# brain_rev_101.net
KiCad netlist of a schematic drawn in EAGLE
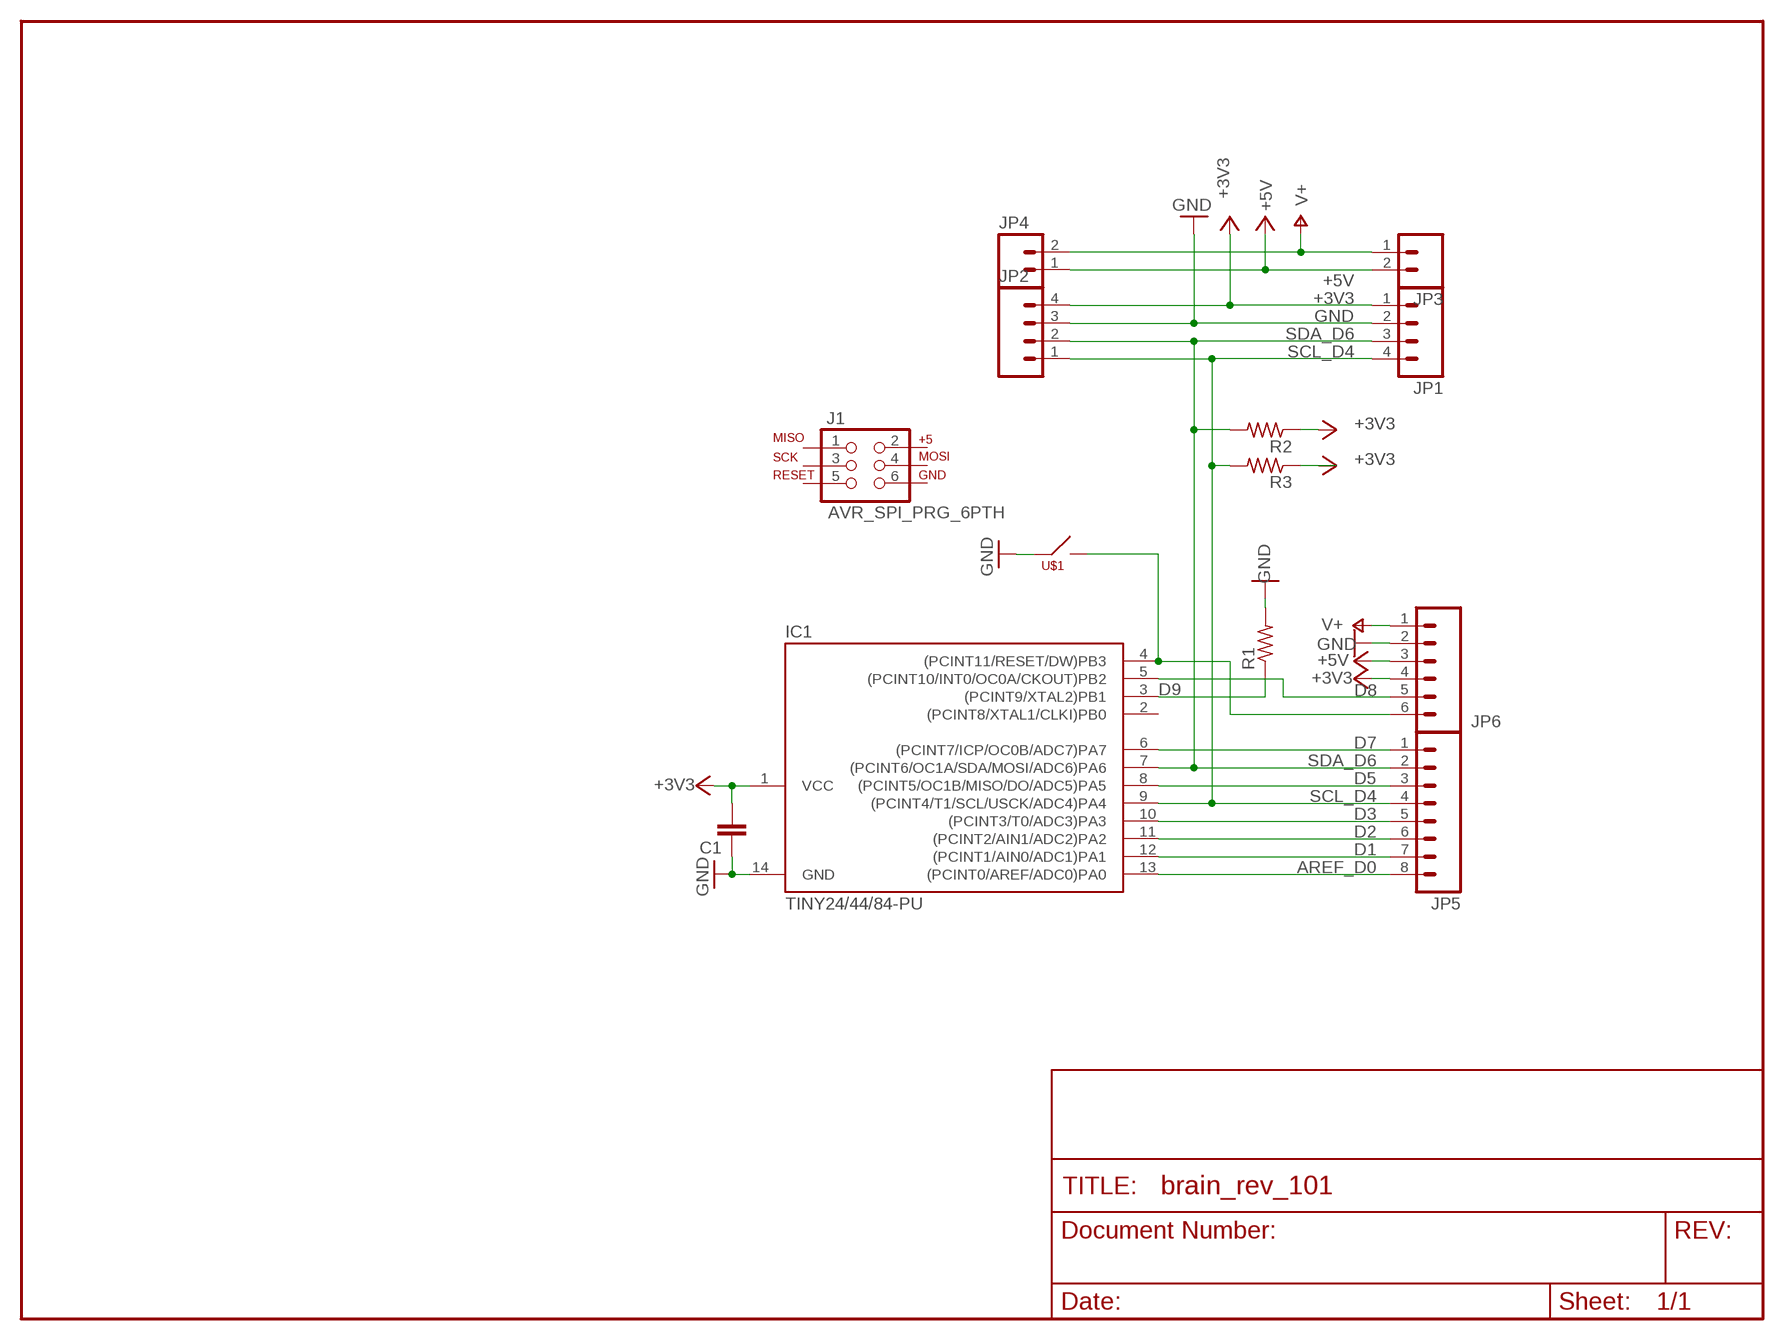
[diagram p0: schematic, sheet 1]

(export (version "E")
  (design (tool "Eeschema 10.0.6"))
  (components
    (comp (ref "C1")
      (value "CAPKIT")
      (footprint "eagle-import:CAP-PTH-SMALL-KIT")
      (libsource (lib "eagle-import") (part "CAPKIT"))
    )
    (comp (ref "IC1")
      (value "TINY24/44/84-PU")
      (footprint "eagle-import:DIL14")
      (libsource (lib "eagle-import") (part "TINY24/44/84-PU"))
    )
    (comp (ref "J1")
      (value "AVR_SPI_PRG_6PTH")
      (footprint "eagle-import:2X3")
      (libsource (lib "eagle-import") (part "AVR_SPI_PRG_6PTH"))
    )
    (comp (ref "JP1")
      (value "M04PTH")
      (footprint "eagle-import:1X04")
      (libsource (lib "eagle-import") (part "M04PTH"))
    )
    (comp (ref "JP2")
      (value "M04PTH")
      (footprint "eagle-import:1X04")
      (libsource (lib "eagle-import") (part "M04PTH"))
    )
    (comp (ref "JP3")
      (value "M02PTH")
      (footprint "eagle-import:1X02")
      (libsource (lib "eagle-import") (part "M02PTH"))
    )
    (comp (ref "JP4")
      (value "M02PTH")
      (footprint "eagle-import:1X02")
      (libsource (lib "eagle-import") (part "M02PTH"))
    )
    (comp (ref "JP5")
      (value "M081X08")
      (footprint "eagle-import:1X08")
      (libsource (lib "eagle-import") (part "M081X08"))
    )
    (comp (ref "JP6")
      (value "M06SIP")
      (footprint "eagle-import:1X06")
      (libsource (lib "eagle-import") (part "M06SIP"))
    )
    (comp (ref "R1")
      (value "R-US_0204/2V")
      (footprint "eagle-import:0204V")
      (libsource (lib "eagle-import") (part "R-US_0204/2V"))
    )
    (comp (ref "R2")
      (value "R-US_0204/2V")
      (footprint "eagle-import:0204V")
      (libsource (lib "eagle-import") (part "R-US_0204/2V"))
    )
    (comp (ref "R3")
      (value "R-US_0204/2V")
      (footprint "eagle-import:0204V")
      (libsource (lib "eagle-import") (part "R-US_0204/2V"))
    )
    (comp (ref "U$1")
      (value "PTS635_SWITCH")
      (footprint "eagle-import:PTS635_SWITCH")
      (libsource (lib "eagle-import") (part "PTS635_SWITCH"))
    )
  )
  (nets
    (net (code "1") (name "+3V3") (class "Default")
      (node (ref "C1") (pin "2") (pinfunction "2_2") (pintype "passive"))
      (node (ref "IC1") (pin "1") (pinfunction "VCC_1") (pintype "power_in"))
      (node (ref "JP1") (pin "1") (pinfunction "1_1") (pintype "passive"))
      (node (ref "JP2") (pin "4") (pinfunction "4_4") (pintype "passive"))
      (node (ref "JP6") (pin "4") (pinfunction "4_4") (pintype "passive"))
      (node (ref "R2") (pin "1") (pinfunction "1_1") (pintype "passive"))
      (node (ref "R3") (pin "1") (pinfunction "1_1") (pintype "passive"))
    )
    (net (code "2") (name "+5V") (class "Default")
      (node (ref "JP3") (pin "2") (pinfunction "2_2") (pintype "passive"))
      (node (ref "JP4") (pin "1") (pinfunction "1_1") (pintype "passive"))
      (node (ref "JP6") (pin "3") (pinfunction "3_3") (pintype "passive"))
    )
    (net (code "3") (name "/AREF_D0") (class "Default")
      (node (ref "IC1") (pin "13") (pinfunction "(PCINT0/AREF/ADC0)PA0_13") (pintype "bidirectional"))
      (node (ref "JP5") (pin "8") (pinfunction "8_8") (pintype "passive"))
    )
    (net (code "4") (name "/D1") (class "Default")
      (node (ref "IC1") (pin "12") (pinfunction "(PCINT1/AIN0/ADC1)PA1_12") (pintype "bidirectional"))
      (node (ref "JP5") (pin "7") (pinfunction "7_7") (pintype "passive"))
    )
    (net (code "5") (name "/D2") (class "Default")
      (node (ref "IC1") (pin "11") (pinfunction "(PCINT2/AIN1/ADC2)PA2_11") (pintype "bidirectional"))
      (node (ref "JP5") (pin "6") (pinfunction "6_6") (pintype "passive"))
    )
    (net (code "6") (name "/D3") (class "Default")
      (node (ref "IC1") (pin "10") (pinfunction "(PCINT3/T0/ADC3)PA3_10") (pintype "bidirectional"))
      (node (ref "JP5") (pin "5") (pinfunction "5_5") (pintype "passive"))
    )
    (net (code "7") (name "/D5") (class "Default")
      (node (ref "IC1") (pin "8") (pinfunction "(PCINT5/OC1B/MISO/DO/ADC5)PA5_8") (pintype "bidirectional"))
      (node (ref "JP5") (pin "3") (pinfunction "3_3") (pintype "passive"))
    )
    (net (code "8") (name "/D7") (class "Default")
      (node (ref "IC1") (pin "6") (pinfunction "(PCINT7/ICP/OC0B/ADC7)PA7_6") (pintype "bidirectional"))
      (node (ref "JP5") (pin "1") (pinfunction "1_1") (pintype "passive"))
    )
    (net (code "9") (name "/D8") (class "Default")
      (node (ref "IC1") (pin "5") (pinfunction "(PCINT10/INT0/OC0A/CKOUT)PB2_5") (pintype "bidirectional"))
      (node (ref "JP6") (pin "5") (pinfunction "5_5") (pintype "passive"))
    )
    (net (code "10") (name "/D9") (class "Default")
      (node (ref "IC1") (pin "3") (pinfunction "(PCINT9/XTAL2)PB1_3") (pintype "bidirectional"))
      (node (ref "R1") (pin "1") (pinfunction "1_1") (pintype "passive"))
    )
    (net (code "11") (name "/SCL_D4") (class "Default")
      (node (ref "IC1") (pin "9") (pinfunction "(PCINT4/T1/SCL/USCK/ADC4)PA4_9") (pintype "bidirectional"))
      (node (ref "JP1") (pin "4") (pinfunction "4_4") (pintype "passive"))
      (node (ref "JP2") (pin "1") (pinfunction "1_1") (pintype "passive"))
      (node (ref "JP5") (pin "4") (pinfunction "4_4") (pintype "passive"))
      (node (ref "R3") (pin "2") (pinfunction "2_2") (pintype "passive"))
    )
    (net (code "12") (name "/SDA_D6") (class "Default")
      (node (ref "IC1") (pin "7") (pinfunction "(PCINT6/OC1A/SDA/MOSI/ADC6)PA6_7") (pintype "bidirectional"))
      (node (ref "JP1") (pin "3") (pinfunction "3_3") (pintype "passive"))
      (node (ref "JP2") (pin "2") (pinfunction "2_2") (pintype "passive"))
      (node (ref "JP5") (pin "2") (pinfunction "2_2") (pintype "passive"))
      (node (ref "R2") (pin "2") (pinfunction "2_2") (pintype "passive"))
    )
    (net (code "13") (name "GND") (class "Default")
      (node (ref "C1") (pin "1") (pinfunction "1_1") (pintype "passive"))
      (node (ref "IC1") (pin "14") (pinfunction "GND_14") (pintype "power_in"))
      (node (ref "JP1") (pin "2") (pinfunction "2_2") (pintype "passive"))
      (node (ref "JP2") (pin "3") (pinfunction "3_3") (pintype "passive"))
      (node (ref "JP6") (pin "2") (pinfunction "2_2") (pintype "passive"))
      (node (ref "R1") (pin "2") (pinfunction "2_2") (pintype "passive"))
      (node (ref "U$1") (pin "P$1") (pinfunction "P$1_P$1") (pintype "bidirectional"))
    )
    (net (code "14") (name "Net-(IC1-(PCINT11{slash}RESET{slash}DW)PB3)") (class "Default")
      (node (ref "IC1") (pin "4") (pinfunction "(PCINT11/RESET/DW)PB3_4") (pintype "bidirectional"))
      (node (ref "JP6") (pin "6") (pinfunction "6_6") (pintype "passive"))
      (node (ref "U$1") (pin "P$2") (pinfunction "P$2_P$2") (pintype "bidirectional"))
    )
    (net (code "15") (name "V+") (class "Default")
      (node (ref "JP3") (pin "1") (pinfunction "1_1") (pintype "passive"))
      (node (ref "JP4") (pin "2") (pinfunction "2_2") (pintype "passive"))
      (node (ref "JP6") (pin "1") (pinfunction "1_1") (pintype "passive"))
    )
    (net (code "16") (name "unconnected-(IC1-(PCINT8{slash}XTAL1{slash}CLKI)PB0-Pad2)") (class "Default")
      (node (ref "IC1") (pin "2") (pinfunction "(PCINT8/XTAL1/CLKI)PB0_2") (pintype "bidirectional"))
    )
    (net (code "17") (name "unconnected-(J1-Pad1)") (class "Default")
      (node (ref "J1") (pin "1") (pinfunction "1_1") (pintype "passive"))
    )
    (net (code "18") (name "unconnected-(J1-Pad2)") (class "Default")
      (node (ref "J1") (pin "2") (pinfunction "2_2") (pintype "passive"))
    )
    (net (code "19") (name "unconnected-(J1-Pad3)") (class "Default")
      (node (ref "J1") (pin "3") (pinfunction "3_3") (pintype "passive"))
    )
    (net (code "20") (name "unconnected-(J1-Pad4)") (class "Default")
      (node (ref "J1") (pin "4") (pinfunction "4_4") (pintype "passive"))
    )
    (net (code "21") (name "unconnected-(J1-Pad5)") (class "Default")
      (node (ref "J1") (pin "5") (pinfunction "5_5") (pintype "passive"))
    )
    (net (code "22") (name "unconnected-(J1-Pad6)") (class "Default")
      (node (ref "J1") (pin "6") (pinfunction "6_6") (pintype "passive"))
    )
  )
)
